# MySensorMicro.net
KiCad netlist of a schematic drawn in EAGLE
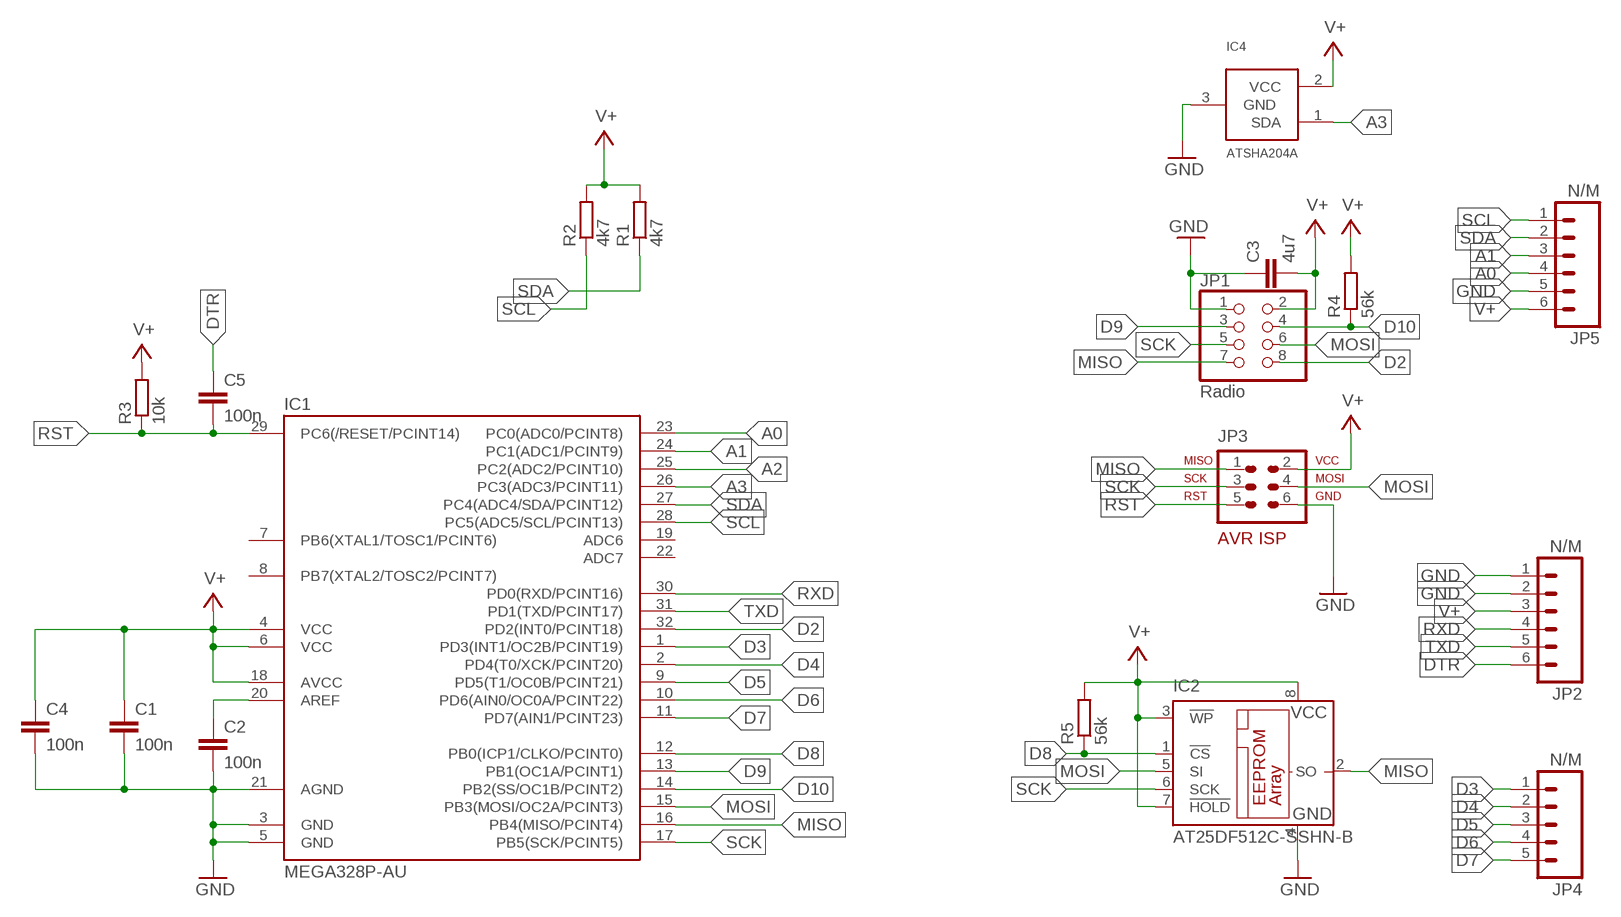
[diagram p0: schematic, sheet 1]

(export (version "E")
  (design (tool "Eeschema 10.0.6"))
  (components
    (comp (ref "C1")
      (value "100n")
      (footprint "eagle-import:C0603K")
      (libsource (lib "eagle-import") (part "C-EUC0603K"))
    )
    (comp (ref "C2")
      (value "100n")
      (footprint "eagle-import:C0603K")
      (libsource (lib "eagle-import") (part "C-EUC0603K"))
    )
    (comp (ref "C3")
      (value "4u7")
      (footprint "eagle-import:C0603K")
      (libsource (lib "eagle-import") (part "C-EUC0603K"))
    )
    (comp (ref "C4")
      (value "100n")
      (footprint "eagle-import:C0603K")
      (libsource (lib "eagle-import") (part "C-EUC0603K"))
    )
    (comp (ref "C5")
      (value "100n")
      (footprint "eagle-import:C0603K")
      (libsource (lib "eagle-import") (part "C-EUC0603K"))
    )
    (comp (ref "IC1")
      (value "MEGA328P-AU")
      (footprint "eagle-import:TQFP32-08")
      (libsource (lib "eagle-import") (part "MEGA48/88/168-AU"))
    )
    (comp (ref "IC2")
      (value "AT25DF512C-SSHN-B")
      (footprint "eagle-import:SO-08")
      (fields (field (name "MF") "MICROCHIP") (field (name "MPN") "25AA080/SN"))
      (libsource (lib "eagle-import") (part "25SNAA080"))
    )
    (comp (ref "IC4")
      (value "ATSHA204A")
      (footprint "eagle-import:SOT23")
      (libsource (lib "eagle-import") (part "ATSHA204A"))
    )
    (comp (ref "JP1")
      (value "Radio")
      (footprint "eagle-import:2X04")
      (libsource (lib "eagle-import") (part "PINHD-2X4"))
    )
    (comp (ref "JP2")
      (value "N/M")
      (footprint "eagle-import:1X06_NO_SILK")
      (libsource (lib "eagle-import") (part "M06NO_SILK_FEMALE_PTH"))
    )
    (comp (ref "JP3")
      (value "N/M")
      (footprint "eagle-import:AVR-ISP-6")
      (libsource (lib "eagle-import") (part "AVR-ISP-6VERT"))
    )
    (comp (ref "JP4")
      (value "N/M")
      (footprint "eagle-import:1X05_NO_SILK")
      (libsource (lib "eagle-import") (part "M05NO_SILK"))
    )
    (comp (ref "JP5")
      (value "N/M")
      (footprint "eagle-import:1X06_NO_SILK")
      (libsource (lib "eagle-import") (part "M06NO_SILK_FEMALE_PTH"))
    )
    (comp (ref "R1")
      (value "4k7")
      (footprint "eagle-import:R0603")
      (libsource (lib "eagle-import") (part "R-EU_R0603"))
    )
    (comp (ref "R2")
      (value "4k7")
      (footprint "eagle-import:R0603")
      (libsource (lib "eagle-import") (part "R-EU_R0603"))
    )
    (comp (ref "R3")
      (value "10k")
      (footprint "eagle-import:R0603")
      (libsource (lib "eagle-import") (part "R-EU_R0603"))
    )
    (comp (ref "R4")
      (value "56k")
      (footprint "eagle-import:R0603")
      (libsource (lib "eagle-import") (part "R-EU_R0603"))
    )
    (comp (ref "R5")
      (value "56k")
      (footprint "eagle-import:R0603")
      (libsource (lib "eagle-import") (part "R-EU_R0603"))
    )
  )
  (nets
    (net (code "1") (name "A0") (class "Default")
      (node (ref "IC1") (pin "23") (pinfunction "PC0(ADC0/PCINT8)_23") (pintype "bidirectional"))
      (node (ref "JP5") (pin "4") (pinfunction "4_4") (pintype "passive"))
    )
    (net (code "2") (name "A1") (class "Default")
      (node (ref "IC1") (pin "24") (pinfunction "PC1(ADC1/PCINT9)_24") (pintype "bidirectional"))
      (node (ref "JP5") (pin "3") (pinfunction "3_3") (pintype "passive"))
    )
    (net (code "3") (name "A2") (class "Default")
      (node (ref "IC1") (pin "25") (pinfunction "PC2(ADC2/PCINT10)_25") (pintype "bidirectional"))
    )
    (net (code "4") (name "A3") (class "Default")
      (node (ref "IC1") (pin "26") (pinfunction "PC3(ADC3/PCINT11)_26") (pintype "bidirectional"))
      (node (ref "IC4") (pin "1") (pinfunction "SDA_1") (pintype "bidirectional"))
    )
    (net (code "5") (name "D2") (class "Default")
      (node (ref "IC1") (pin "32") (pinfunction "PD2(INT0/PCINT18)_32") (pintype "bidirectional"))
      (node (ref "JP1") (pin "8") (pinfunction "8_8") (pintype "passive"))
    )
    (net (code "6") (name "D3") (class "Default")
      (node (ref "IC1") (pin "1") (pinfunction "PD3(INT1/OC2B/PCINT19)_1") (pintype "bidirectional"))
      (node (ref "JP4") (pin "1") (pinfunction "1_1") (pintype "passive"))
    )
    (net (code "7") (name "D4") (class "Default")
      (node (ref "IC1") (pin "2") (pinfunction "PD4(T0/XCK/PCINT20)_2") (pintype "bidirectional"))
      (node (ref "JP4") (pin "2") (pinfunction "2_2") (pintype "passive"))
    )
    (net (code "8") (name "D5") (class "Default")
      (node (ref "IC1") (pin "9") (pinfunction "PD5(T1/OC0B/PCINT21)_9") (pintype "bidirectional"))
      (node (ref "JP4") (pin "3") (pinfunction "3_3") (pintype "passive"))
    )
    (net (code "9") (name "D6") (class "Default")
      (node (ref "IC1") (pin "10") (pinfunction "PD6(AIN0/OC0A/PCINT22)_10") (pintype "bidirectional"))
      (node (ref "JP4") (pin "4") (pinfunction "4_4") (pintype "passive"))
    )
    (net (code "10") (name "D7") (class "Default")
      (node (ref "IC1") (pin "11") (pinfunction "PD7(AIN1/PCINT23)_11") (pintype "bidirectional"))
      (node (ref "JP4") (pin "5") (pinfunction "5_5") (pintype "passive"))
    )
    (net (code "11") (name "D8") (class "Default")
      (node (ref "IC1") (pin "12") (pinfunction "PB0(ICP1/CLKO/PCINT0)_12") (pintype "bidirectional"))
      (node (ref "IC2") (pin "1") (pinfunction "~{CS}_1") (pintype "input"))
      (node (ref "R5") (pin "1") (pinfunction "1_1") (pintype "passive"))
    )
    (net (code "12") (name "D9") (class "Default")
      (node (ref "IC1") (pin "13") (pinfunction "PB1(OC1A/PCINT1)_13") (pintype "bidirectional"))
      (node (ref "JP1") (pin "3") (pinfunction "3_3") (pintype "passive"))
    )
    (net (code "13") (name "D10") (class "Default")
      (node (ref "IC1") (pin "14") (pinfunction "PB2(SS/OC1B/PCINT2)_14") (pintype "bidirectional"))
      (node (ref "JP1") (pin "4") (pinfunction "4_4") (pintype "passive"))
      (node (ref "R4") (pin "1") (pinfunction "1_1") (pintype "passive"))
    )
    (net (code "14") (name "DTR") (class "Default")
      (node (ref "C5") (pin "1") (pinfunction "1_1") (pintype "passive"))
      (node (ref "JP2") (pin "6") (pinfunction "6_6") (pintype "passive"))
    )
    (net (code "15") (name "GND") (class "Default")
      (node (ref "C1") (pin "2") (pinfunction "2_2") (pintype "passive"))
      (node (ref "C2") (pin "2") (pinfunction "2_2") (pintype "passive"))
      (node (ref "C3") (pin "1") (pinfunction "1_1") (pintype "passive"))
      (node (ref "C4") (pin "2") (pinfunction "2_2") (pintype "passive"))
      (node (ref "IC1") (pin "21") (pinfunction "AGND_21") (pintype "power_in"))
      (node (ref "IC1") (pin "3") (pinfunction "GND_3") (pintype "power_in"))
      (node (ref "IC1") (pin "5") (pinfunction "GND_5") (pintype "power_in"))
      (node (ref "IC2") (pin "4") (pinfunction "GND_4") (pintype "power_in"))
      (node (ref "IC4") (pin "3") (pinfunction "GND_3") (pintype "bidirectional"))
      (node (ref "JP1") (pin "1") (pinfunction "1_1") (pintype "passive"))
      (node (ref "JP2") (pin "1") (pinfunction "1_1") (pintype "passive"))
      (node (ref "JP2") (pin "2") (pinfunction "2_2") (pintype "passive"))
      (node (ref "JP3") (pin "6") (pinfunction "6_6") (pintype "passive"))
      (node (ref "JP5") (pin "5") (pinfunction "5_5") (pintype "passive"))
    )
    (net (code "16") (name "MISO") (class "Default")
      (node (ref "IC1") (pin "16") (pinfunction "PB4(MISO/PCINT4)_16") (pintype "bidirectional"))
      (node (ref "IC2") (pin "2") (pinfunction "SO_2") (pintype "bidirectional"))
      (node (ref "JP1") (pin "7") (pinfunction "7_7") (pintype "passive"))
      (node (ref "JP3") (pin "1") (pinfunction "1_1") (pintype "passive"))
    )
    (net (code "17") (name "MOSI") (class "Default")
      (node (ref "IC1") (pin "15") (pinfunction "PB3(MOSI/OC2A/PCINT3)_15") (pintype "bidirectional"))
      (node (ref "IC2") (pin "5") (pinfunction "SI_5") (pintype "input"))
      (node (ref "JP1") (pin "6") (pinfunction "6_6") (pintype "passive"))
      (node (ref "JP3") (pin "4") (pinfunction "4_4") (pintype "passive"))
    )
    (net (code "18") (name "Net-(IC1-AREF)") (class "Default")
      (node (ref "C2") (pin "1") (pinfunction "1_1") (pintype "passive"))
      (node (ref "IC1") (pin "20") (pinfunction "AREF_20") (pintype "passive"))
    )
    (net (code "19") (name "RST") (class "Default")
      (node (ref "C5") (pin "2") (pinfunction "2_2") (pintype "passive"))
      (node (ref "IC1") (pin "29") (pinfunction "PC6(/RESET/PCINT14)_29") (pintype "bidirectional"))
      (node (ref "JP3") (pin "5") (pinfunction "5_5") (pintype "passive"))
      (node (ref "R3") (pin "1") (pinfunction "1_1") (pintype "passive"))
    )
    (net (code "20") (name "RXD") (class "Default")
      (node (ref "IC1") (pin "30") (pinfunction "PD0(RXD/PCINT16)_30") (pintype "bidirectional"))
      (node (ref "JP2") (pin "4") (pinfunction "4_4") (pintype "passive"))
    )
    (net (code "21") (name "SCK") (class "Default")
      (node (ref "IC1") (pin "17") (pinfunction "PB5(SCK/PCINT5)_17") (pintype "bidirectional"))
      (node (ref "IC2") (pin "6") (pinfunction "SCK_6") (pintype "input"))
      (node (ref "JP1") (pin "5") (pinfunction "5_5") (pintype "passive"))
      (node (ref "JP3") (pin "3") (pinfunction "3_3") (pintype "passive"))
    )
    (net (code "22") (name "SCL") (class "Default")
      (node (ref "IC1") (pin "28") (pinfunction "PC5(ADC5/SCL/PCINT13)_28") (pintype "bidirectional"))
      (node (ref "JP5") (pin "1") (pinfunction "1_1") (pintype "passive"))
      (node (ref "R2") (pin "1") (pinfunction "1_1") (pintype "passive"))
    )
    (net (code "23") (name "SDA") (class "Default")
      (node (ref "IC1") (pin "27") (pinfunction "PC4(ADC4/SDA/PCINT12)_27") (pintype "bidirectional"))
      (node (ref "JP5") (pin "2") (pinfunction "2_2") (pintype "passive"))
      (node (ref "R1") (pin "1") (pinfunction "1_1") (pintype "passive"))
    )
    (net (code "24") (name "TXD") (class "Default")
      (node (ref "IC1") (pin "31") (pinfunction "PD1(TXD/PCINT17)_31") (pintype "bidirectional"))
      (node (ref "JP2") (pin "5") (pinfunction "5_5") (pintype "passive"))
    )
    (net (code "25") (name "V+") (class "Default")
      (node (ref "C1") (pin "1") (pinfunction "1_1") (pintype "passive"))
      (node (ref "C3") (pin "2") (pinfunction "2_2") (pintype "passive"))
      (node (ref "C4") (pin "1") (pinfunction "1_1") (pintype "passive"))
      (node (ref "IC1") (pin "18") (pinfunction "AVCC_18") (pintype "passive"))
      (node (ref "IC1") (pin "4") (pinfunction "VCC_4") (pintype "power_in"))
      (node (ref "IC1") (pin "6") (pinfunction "VCC_6") (pintype "power_in"))
      (node (ref "IC2") (pin "3") (pinfunction "~{WP}_3") (pintype "input"))
      (node (ref "IC2") (pin "7") (pinfunction "~{HOLD}_7") (pintype "input"))
      (node (ref "IC2") (pin "8") (pinfunction "VCC_8") (pintype "power_in"))
      (node (ref "IC4") (pin "2") (pinfunction "VCC_2") (pintype "bidirectional"))
      (node (ref "JP1") (pin "2") (pinfunction "2_2") (pintype "passive"))
      (node (ref "JP2") (pin "3") (pinfunction "3_3") (pintype "passive"))
      (node (ref "JP3") (pin "2") (pinfunction "2_2") (pintype "passive"))
      (node (ref "JP5") (pin "6") (pinfunction "6_6") (pintype "passive"))
      (node (ref "R1") (pin "2") (pinfunction "2_2") (pintype "passive"))
      (node (ref "R2") (pin "2") (pinfunction "2_2") (pintype "passive"))
      (node (ref "R3") (pin "2") (pinfunction "2_2") (pintype "passive"))
      (node (ref "R4") (pin "2") (pinfunction "2_2") (pintype "passive"))
      (node (ref "R5") (pin "2") (pinfunction "2_2") (pintype "passive"))
    )
    (net (code "26") (name "unconnected-(IC1-ADC6-Pad19)") (class "Default")
      (node (ref "IC1") (pin "19") (pinfunction "ADC6_19") (pintype "passive"))
    )
    (net (code "27") (name "unconnected-(IC1-ADC7-Pad22)") (class "Default")
      (node (ref "IC1") (pin "22") (pinfunction "ADC7_22") (pintype "passive"))
    )
    (net (code "28") (name "unconnected-(IC1-PB6(XTAL1{slash}TOSC1{slash}PCINT6)-Pad7)") (class "Default")
      (node (ref "IC1") (pin "7") (pinfunction "PB6(XTAL1/TOSC1/PCINT6)_7") (pintype "bidirectional"))
    )
    (net (code "29") (name "unconnected-(IC1-PB7(XTAL2{slash}TOSC2{slash}PCINT7)-Pad8)") (class "Default")
      (node (ref "IC1") (pin "8") (pinfunction "PB7(XTAL2/TOSC2/PCINT7)_8") (pintype "bidirectional"))
    )
  )
)
